# 01_MAIN.net
KiCad netlist of a schematic drawn in Altium Designer
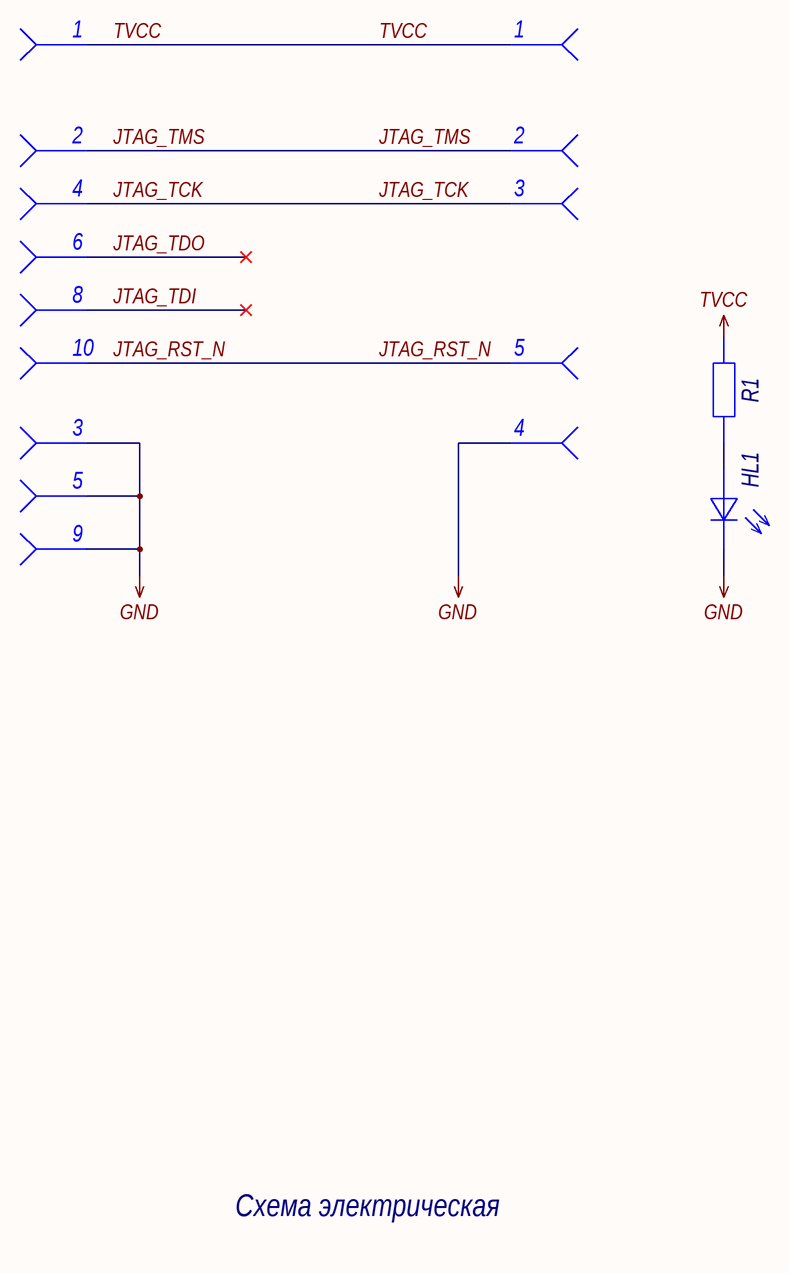
[diagram p0: 01_MAIN.SchDoc]

(export (version "E")
  (design (tool "Eeschema 10.0.6"))
  (components
    (comp (ref "HL1")
      (value "TVCC")
      (footprint "LD0402_L")
      (fields
        (field (name "PART NUMBER") "KPHHS-1005QBC-D-V")
        (field (name "MANUFACTURER") "Kingbright")
        (field (name "PUBLISHER") "Andrew Danich")
      )
      (libsource (lib "ADLib") (part "Led-1"))
    )
    (comp (ref "R1")
      (value "Resistor")
      (footprint "R0402_L")
      (fields
        (field (name "PART NUMBER") "RC0402JR-0710KL")
        (field (name "TOLERANCE") "±5%")
        (field (name "MANUFACTURER") "Yageo")
        (field (name "PUBLISHER") "Andrew Danich")
      )
      (libsource (lib "ADLib") (part "Resistor"))
    )
    (comp (ref "XS1")
      (value "JTAG")
      (footprint "XF2M-1015-1A")
      (fields
        (field (name "PART NUMBER") "XF2M-1015-1A")
        (field (name "MANUFACTURER") "Omron Electronics")
        (field (name "PUBLISHER") "Viktor Klishin")
      )
      (libsource (lib "ADLib") (part "Con-10-F_S"))
    )
    (comp (ref "XS2")
      (value "SWD")
      (footprint "PBS-5")
      (fields (field (name "PUBLISHER") "Andrew Danich"))
      (libsource (lib "Schlib") (part "PBS-5_S"))
    )
  )
  (nets
    (net (code "1") (name "/JTAG_RST_N") (class "Default")
      (node (ref "XS1") (pin "10") (pintype "passive"))
      (node (ref "XS2") (pin "5") (pintype "passive"))
    )
    (net (code "2") (name "/JTAG_TCK") (class "Default")
      (node (ref "XS1") (pin "4") (pintype "passive"))
      (node (ref "XS2") (pin "3") (pintype "passive"))
    )
    (net (code "3") (name "/JTAG_TDI") (class "Default")
      (node (ref "XS1") (pin "8") (pintype "passive+no_connect"))
    )
    (net (code "4") (name "/JTAG_TDO") (class "Default")
      (node (ref "XS1") (pin "6") (pintype "passive+no_connect"))
    )
    (net (code "5") (name "/JTAG_TMS") (class "Default")
      (node (ref "XS1") (pin "2") (pintype "passive"))
      (node (ref "XS2") (pin "2") (pintype "passive"))
    )
    (net (code "6") (name "GND") (class "Default")
      (node (ref "HL1") (pin "2") (pinfunction "К_2") (pintype "passive"))
      (node (ref "XS1") (pin "3") (pintype "passive"))
      (node (ref "XS1") (pin "5") (pintype "passive"))
      (node (ref "XS1") (pin "9") (pintype "passive"))
      (node (ref "XS2") (pin "4") (pintype "passive"))
    )
    (net (code "7") (name "Net-(HL1-А)") (class "Default")
      (node (ref "HL1") (pin "1") (pinfunction "А_1") (pintype "passive"))
      (node (ref "R1") (pin "1") (pinfunction "1_1") (pintype "passive"))
    )
    (net (code "8") (name "TVCC") (class "Default")
      (node (ref "R1") (pin "2") (pinfunction "2_2") (pintype "passive"))
      (node (ref "XS1") (pin "1") (pintype "passive"))
      (node (ref "XS2") (pin "1") (pintype "passive"))
    )
  )
)
